# LED_Running_Light.net
KiCad netlist of a schematic drawn in Altium Designer
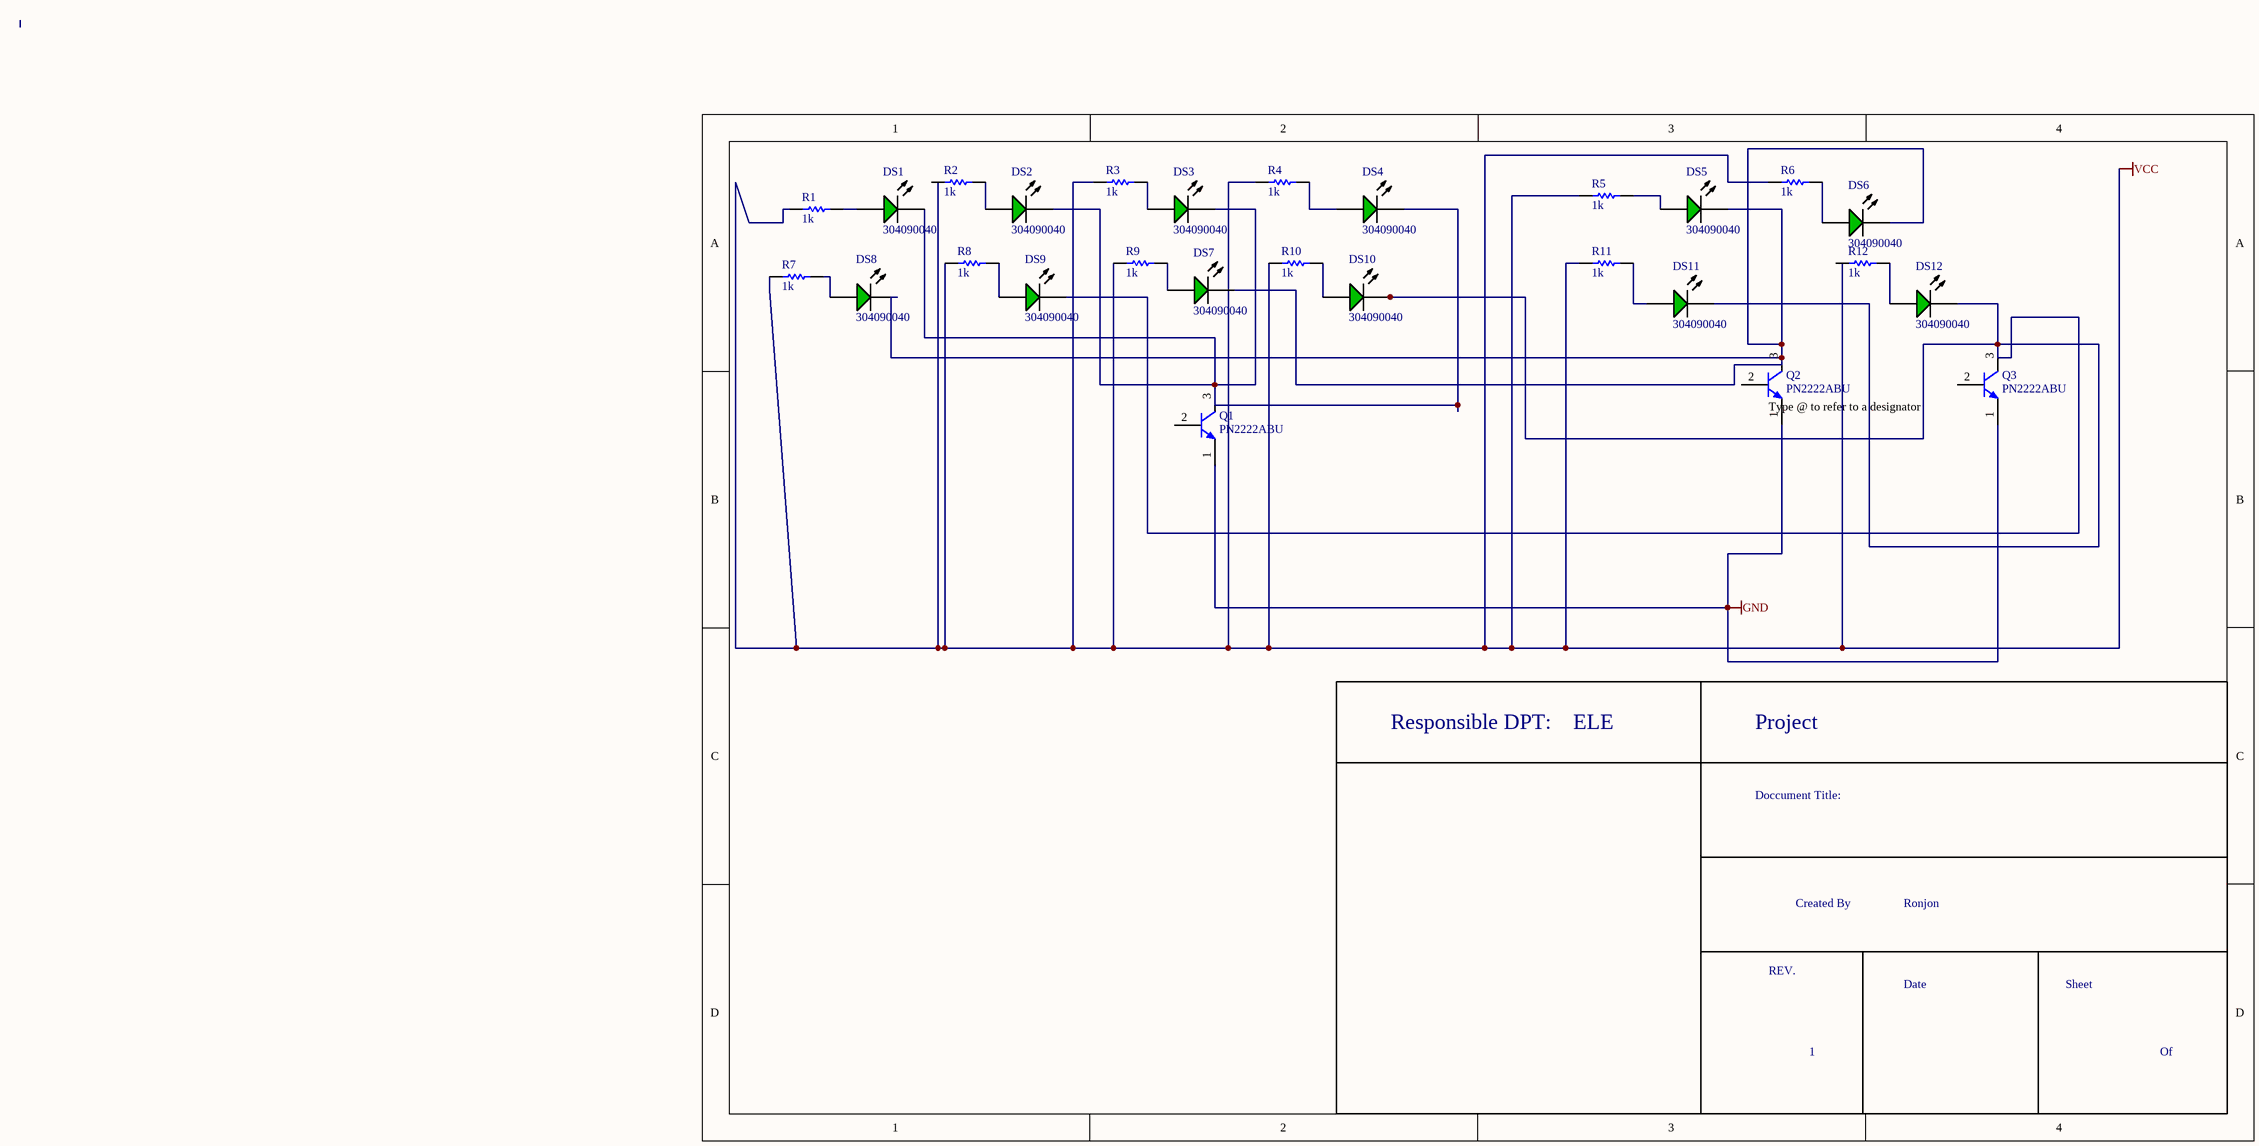
[diagram p0: LED_Running_Light.SchDoc]

(export (version "E")
  (design (tool "Eeschema 10.0.6"))
  (components
    (comp (ref "DS1")
      (value "304090040")
      (footprint "LED-2P-2.28-3MM")
      (description "Green LED, 80 mW, 20 mA, -25 to 85 degC, 2-Pin THD")
      (fields (field (name "MANUFACTURER") "Shenzhen CGX"))
      (libsource (lib "Ronjon Sarker") (part "LED-GREEN-AK-2"))
    )
    (comp (ref "DS2")
      (value "304090040")
      (footprint "LED-2P-2.28-3MM")
      (description "Green LED, 80 mW, 20 mA, -25 to 85 degC, 2-Pin THD")
      (fields (field (name "MANUFACTURER") "Shenzhen CGX"))
      (libsource (lib "Ronjon Sarker") (part "LED-GREEN-AK-2"))
    )
    (comp (ref "DS3")
      (value "304090040")
      (footprint "LED-2P-2.28-3MM")
      (description "Green LED, 80 mW, 20 mA, -25 to 85 degC, 2-Pin THD")
      (fields (field (name "MANUFACTURER") "Shenzhen CGX"))
      (libsource (lib "Ronjon Sarker") (part "LED-GREEN-AK-2"))
    )
    (comp (ref "DS4")
      (value "304090040")
      (footprint "LED-2P-2.28-3MM")
      (description "Green LED, 80 mW, 20 mA, -25 to 85 degC, 2-Pin THD")
      (fields (field (name "MANUFACTURER") "Shenzhen CGX"))
      (libsource (lib "Ronjon Sarker") (part "LED-GREEN-AK-2"))
    )
    (comp (ref "DS5")
      (value "304090040")
      (footprint "LED-2P-2.28-3MM")
      (description "Green LED, 80 mW, 20 mA, -25 to 85 degC, 2-Pin THD")
      (fields (field (name "MANUFACTURER") "Shenzhen CGX"))
      (libsource (lib "Ronjon Sarker") (part "LED-GREEN-AK-2"))
    )
    (comp (ref "DS6")
      (value "304090040")
      (footprint "LED-2P-2.28-3MM")
      (description "Green LED, 80 mW, 20 mA, -25 to 85 degC, 2-Pin THD")
      (fields (field (name "MANUFACTURER") "Shenzhen CGX"))
      (libsource (lib "Ronjon Sarker") (part "LED-GREEN-AK-2"))
    )
    (comp (ref "DS7")
      (value "304090040")
      (footprint "LED-2P-2.28-3MM")
      (description "Green LED, 80 mW, 20 mA, -25 to 85 degC, 2-Pin THD")
      (fields (field (name "MANUFACTURER") "Shenzhen CGX"))
      (libsource (lib "Ronjon Sarker") (part "LED-GREEN-AK-2"))
    )
    (comp (ref "DS8")
      (value "304090040")
      (footprint "LED-2P-2.28-3MM")
      (description "Green LED, 80 mW, 20 mA, -25 to 85 degC, 2-Pin THD")
      (fields (field (name "MANUFACTURER") "Shenzhen CGX"))
      (libsource (lib "Ronjon Sarker") (part "LED-GREEN-AK-2"))
    )
    (comp (ref "DS9")
      (value "304090040")
      (footprint "LED-2P-2.28-3MM")
      (description "Green LED, 80 mW, 20 mA, -25 to 85 degC, 2-Pin THD")
      (fields (field (name "MANUFACTURER") "Shenzhen CGX"))
      (libsource (lib "Ronjon Sarker") (part "LED-GREEN-AK-2"))
    )
    (comp (ref "DS10")
      (value "304090040")
      (footprint "LED-2P-2.28-3MM")
      (description "Green LED, 80 mW, 20 mA, -25 to 85 degC, 2-Pin THD")
      (fields (field (name "MANUFACTURER") "Shenzhen CGX"))
      (libsource (lib "Ronjon Sarker") (part "LED-GREEN-AK-2"))
    )
    (comp (ref "DS11")
      (value "304090040")
      (footprint "LED-2P-2.28-3MM")
      (description "Green LED, 80 mW, 20 mA, -25 to 85 degC, 2-Pin THD")
      (fields (field (name "MANUFACTURER") "Shenzhen CGX"))
      (libsource (lib "Ronjon Sarker") (part "LED-GREEN-AK-2"))
    )
    (comp (ref "DS12")
      (value "304090040")
      (footprint "LED-2P-2.28-3MM")
      (description "Green LED, 80 mW, 20 mA, -25 to 85 degC, 2-Pin THD")
      (fields (field (name "MANUFACTURER") "Shenzhen CGX"))
      (libsource (lib "Ronjon Sarker") (part "LED-GREEN-AK-2"))
    )
    (comp (ref "Q1")
      (value "PN2222ABU")
      (footprint "FAIR-TO-92")
      (description "NPN General-Purpose Amplifier, 40 V, -55 to 150 degC, 3-Pin TO-92, RoHS, Bulk")
      (fields (field (name "POWER") "625mW") (field (name "MANUFACTURER") "Fairchild"))
      (libsource (lib "Ronjon Sarker") (part "BJT-NPN-EBC-3"))
    )
    (comp (ref "Q2")
      (value "PN2222ABU")
      (footprint "FAIR-TO-92")
      (description "NPN General-Purpose Amplifier, 40 V, -55 to 150 degC, 3-Pin TO-92, RoHS, Bulk")
      (fields (field (name "POWER") "625mW") (field (name "MANUFACTURER") "Fairchild"))
      (libsource (lib "Ronjon Sarker") (part "BJT-NPN-EBC-3"))
    )
    (comp (ref "Q3")
      (value "PN2222ABU")
      (footprint "FAIR-TO-92")
      (description "NPN General-Purpose Amplifier, 40 V, -55 to 150 degC, 3-Pin TO-92, RoHS, Bulk")
      (fields (field (name "POWER") "625mW") (field (name "MANUFACTURER") "Fairchild"))
      (libsource (lib "Ronjon Sarker") (part "BJT-NPN-EBC-3"))
    )
    (comp (ref "R1")
      (value "1k")
      (footprint "RESC3116X70X50ML13T20")
      (description "Chip Resistor, 1 KOhm, +/- 1%, 0.25 W, -55 to 155 degC, 1206 (3216 Metric)")
      (fields (field (name "TOLERANCE") "1%") (field (name "POWER") "250mW"))
      (libsource (lib "Ronjon Sarker") (part "RES-2"))
    )
    (comp (ref "R2")
      (value "1k")
      (footprint "RESC3116X70X50ML13T20")
      (description "Chip Resistor, 1 KOhm, +/- 1%, 0.25 W, -55 to 155 degC, 1206 (3216 Metric)")
      (fields (field (name "TOLERANCE") "1%") (field (name "POWER") "250mW"))
      (libsource (lib "Ronjon Sarker") (part "RES-2"))
    )
    (comp (ref "R3")
      (value "1k")
      (footprint "RESC3116X70X50ML13T20")
      (description "Chip Resistor, 1 KOhm, +/- 1%, 0.25 W, -55 to 155 degC, 1206 (3216 Metric)")
      (fields (field (name "TOLERANCE") "1%") (field (name "POWER") "250mW"))
      (libsource (lib "Ronjon Sarker") (part "RES-2"))
    )
    (comp (ref "R4")
      (value "1k")
      (footprint "RESC3116X70X50ML13T20")
      (description "Chip Resistor, 1 KOhm, +/- 1%, 0.25 W, -55 to 155 degC, 1206 (3216 Metric)")
      (fields (field (name "TOLERANCE") "1%") (field (name "POWER") "250mW"))
      (libsource (lib "Ronjon Sarker") (part "RES-2"))
    )
    (comp (ref "R5")
      (value "1k")
      (footprint "RESC3116X70X50ML13T20")
      (description "Chip Resistor, 1 KOhm, +/- 1%, 0.25 W, -55 to 155 degC, 1206 (3216 Metric)")
      (fields (field (name "TOLERANCE") "1%") (field (name "POWER") "250mW"))
      (libsource (lib "Ronjon Sarker") (part "RES-2"))
    )
    (comp (ref "R6")
      (value "1k")
      (footprint "RESC3116X70X50ML13T20")
      (description "Chip Resistor, 1 KOhm, +/- 1%, 0.25 W, -55 to 155 degC, 1206 (3216 Metric)")
      (fields (field (name "TOLERANCE") "1%") (field (name "POWER") "250mW"))
      (libsource (lib "Ronjon Sarker") (part "RES-2"))
    )
    (comp (ref "R7")
      (value "1k")
      (footprint "RESC3116X70X50ML13T20")
      (description "Chip Resistor, 1 KOhm, +/- 1%, 0.25 W, -55 to 155 degC, 1206 (3216 Metric)")
      (fields (field (name "TOLERANCE") "1%") (field (name "POWER") "250mW"))
      (libsource (lib "Ronjon Sarker") (part "RES-2"))
    )
    (comp (ref "R8")
      (value "1k")
      (footprint "RESC3116X70X50ML13T20")
      (description "Chip Resistor, 1 KOhm, +/- 1%, 0.25 W, -55 to 155 degC, 1206 (3216 Metric)")
      (fields (field (name "TOLERANCE") "1%") (field (name "POWER") "250mW"))
      (libsource (lib "Ronjon Sarker") (part "RES-2"))
    )
    (comp (ref "R9")
      (value "1k")
      (footprint "RESC3116X70X50ML13T20")
      (description "Chip Resistor, 1 KOhm, +/- 1%, 0.25 W, -55 to 155 degC, 1206 (3216 Metric)")
      (fields (field (name "TOLERANCE") "1%") (field (name "POWER") "250mW"))
      (libsource (lib "Ronjon Sarker") (part "RES-2"))
    )
    (comp (ref "R10")
      (value "1k")
      (footprint "RESC3116X70X50ML13T20")
      (description "Chip Resistor, 1 KOhm, +/- 1%, 0.25 W, -55 to 155 degC, 1206 (3216 Metric)")
      (fields (field (name "TOLERANCE") "1%") (field (name "POWER") "250mW"))
      (libsource (lib "Ronjon Sarker") (part "RES-2"))
    )
    (comp (ref "R11")
      (value "1k")
      (footprint "RESC3116X70X50ML13T20")
      (description "Chip Resistor, 1 KOhm, +/- 1%, 0.25 W, -55 to 155 degC, 1206 (3216 Metric)")
      (fields (field (name "TOLERANCE") "1%") (field (name "POWER") "250mW"))
      (libsource (lib "Ronjon Sarker") (part "RES-2"))
    )
    (comp (ref "R12")
      (value "1k")
      (footprint "RESC3116X70X50ML13T20")
      (description "Chip Resistor, 1 KOhm, +/- 1%, 0.25 W, -55 to 155 degC, 1206 (3216 Metric)")
      (fields (field (name "TOLERANCE") "1%") (field (name "POWER") "250mW"))
      (libsource (lib "Ronjon Sarker") (part "RES-2"))
    )
  )
  (nets
    (net (code "1") (name "GND") (class "Default")
      (node (ref "Q1") (pin "1") (pinfunction "E_1") (pintype "passive"))
      (node (ref "Q2") (pin "1") (pinfunction "E_1") (pintype "passive"))
      (node (ref "Q3") (pin "1") (pinfunction "E_1") (pintype "passive"))
    )
    (net (code "2") (name "Net-(DS1-A)") (class "Default")
      (node (ref "DS1") (pin "1") (pinfunction "A_1") (pintype "passive"))
      (node (ref "R1") (pin "2") (pinfunction "2_2") (pintype "passive"))
    )
    (net (code "3") (name "Net-(DS1-K)") (class "Default")
      (node (ref "DS1") (pin "2") (pinfunction "K_2") (pintype "passive"))
      (node (ref "DS2") (pin "2") (pinfunction "K_2") (pintype "passive"))
      (node (ref "DS3") (pin "2") (pinfunction "K_2") (pintype "passive"))
      (node (ref "DS4") (pin "2") (pinfunction "K_2") (pintype "passive"))
      (node (ref "Q1") (pin "3") (pinfunction "C_3") (pintype "passive"))
    )
    (net (code "4") (name "Net-(DS2-A)") (class "Default")
      (node (ref "DS2") (pin "1") (pinfunction "A_1") (pintype "passive"))
      (node (ref "R2") (pin "2") (pinfunction "2_2") (pintype "passive"))
    )
    (net (code "5") (name "Net-(DS3-A)") (class "Default")
      (node (ref "DS3") (pin "1") (pinfunction "A_1") (pintype "passive"))
      (node (ref "R3") (pin "2") (pinfunction "2_2") (pintype "passive"))
    )
    (net (code "6") (name "Net-(DS4-A)") (class "Default")
      (node (ref "DS4") (pin "1") (pinfunction "A_1") (pintype "passive"))
      (node (ref "R4") (pin "2") (pinfunction "2_2") (pintype "passive"))
    )
    (net (code "7") (name "Net-(DS5-A)") (class "Default")
      (node (ref "DS5") (pin "1") (pinfunction "A_1") (pintype "passive"))
      (node (ref "R5") (pin "2") (pinfunction "2_2") (pintype "passive"))
    )
    (net (code "8") (name "Net-(DS5-K)") (class "Default")
      (node (ref "DS5") (pin "2") (pinfunction "K_2") (pintype "passive"))
      (node (ref "DS6") (pin "2") (pinfunction "K_2") (pintype "passive"))
      (node (ref "DS7") (pin "2") (pinfunction "K_2") (pintype "passive"))
      (node (ref "DS8") (pin "2") (pinfunction "K_2") (pintype "passive"))
      (node (ref "Q2") (pin "3") (pinfunction "C_3") (pintype "passive"))
    )
    (net (code "9") (name "Net-(DS6-A)") (class "Default")
      (node (ref "DS6") (pin "1") (pinfunction "A_1") (pintype "passive"))
      (node (ref "R6") (pin "2") (pinfunction "2_2") (pintype "passive"))
    )
    (net (code "10") (name "Net-(DS7-A)") (class "Default")
      (node (ref "DS7") (pin "1") (pinfunction "A_1") (pintype "passive"))
      (node (ref "R9") (pin "2") (pinfunction "2_2") (pintype "passive"))
    )
    (net (code "11") (name "Net-(DS8-A)") (class "Default")
      (node (ref "DS8") (pin "1") (pinfunction "A_1") (pintype "passive"))
      (node (ref "R7") (pin "2") (pinfunction "2_2") (pintype "passive"))
    )
    (net (code "12") (name "Net-(DS9-A)") (class "Default")
      (node (ref "DS9") (pin "1") (pinfunction "A_1") (pintype "passive"))
      (node (ref "R8") (pin "2") (pinfunction "2_2") (pintype "passive"))
    )
    (net (code "13") (name "Net-(DS10-A)") (class "Default")
      (node (ref "DS10") (pin "1") (pinfunction "A_1") (pintype "passive"))
      (node (ref "R10") (pin "2") (pinfunction "2_2") (pintype "passive"))
    )
    (net (code "14") (name "Net-(DS10-K)") (class "Default")
      (node (ref "DS10") (pin "2") (pinfunction "K_2") (pintype "passive"))
      (node (ref "DS11") (pin "2") (pinfunction "K_2") (pintype "passive"))
      (node (ref "DS12") (pin "2") (pinfunction "K_2") (pintype "passive"))
      (node (ref "DS9") (pin "2") (pinfunction "K_2") (pintype "passive"))
      (node (ref "Q3") (pin "3") (pinfunction "C_3") (pintype "passive"))
    )
    (net (code "15") (name "Net-(DS11-A)") (class "Default")
      (node (ref "DS11") (pin "1") (pinfunction "A_1") (pintype "passive"))
      (node (ref "R11") (pin "2") (pinfunction "2_2") (pintype "passive"))
    )
    (net (code "16") (name "Net-(DS12-A)") (class "Default")
      (node (ref "DS12") (pin "1") (pinfunction "A_1") (pintype "passive"))
      (node (ref "R12") (pin "2") (pinfunction "2_2") (pintype "passive"))
    )
    (net (code "17") (name "VCC") (class "Default")
      (node (ref "R1") (pin "1") (pinfunction "1_1") (pintype "passive"))
      (node (ref "R10") (pin "1") (pinfunction "1_1") (pintype "passive"))
      (node (ref "R11") (pin "1") (pinfunction "1_1") (pintype "passive"))
      (node (ref "R12") (pin "1") (pinfunction "1_1") (pintype "passive"))
      (node (ref "R2") (pin "1") (pinfunction "1_1") (pintype "passive"))
      (node (ref "R3") (pin "1") (pinfunction "1_1") (pintype "passive"))
      (node (ref "R4") (pin "1") (pinfunction "1_1") (pintype "passive"))
      (node (ref "R5") (pin "1") (pinfunction "1_1") (pintype "passive"))
      (node (ref "R6") (pin "1") (pinfunction "1_1") (pintype "passive"))
      (node (ref "R7") (pin "1") (pinfunction "1_1") (pintype "passive"))
      (node (ref "R8") (pin "1") (pinfunction "1_1") (pintype "passive"))
      (node (ref "R9") (pin "1") (pinfunction "1_1") (pintype "passive"))
    )
    (net (code "18") (name "unconnected-(Q1-B-Pad2)") (class "Default")
      (node (ref "Q1") (pin "2") (pinfunction "B_2") (pintype "passive"))
    )
    (net (code "19") (name "unconnected-(Q2-B-Pad2)") (class "Default")
      (node (ref "Q2") (pin "2") (pinfunction "B_2") (pintype "passive"))
    )
    (net (code "20") (name "unconnected-(Q3-B-Pad2)") (class "Default")
      (node (ref "Q3") (pin "2") (pinfunction "B_2") (pintype "passive"))
    )
  )
)
